# avr_plc.net
KiCad netlist of a schematic drawn in EAGLE
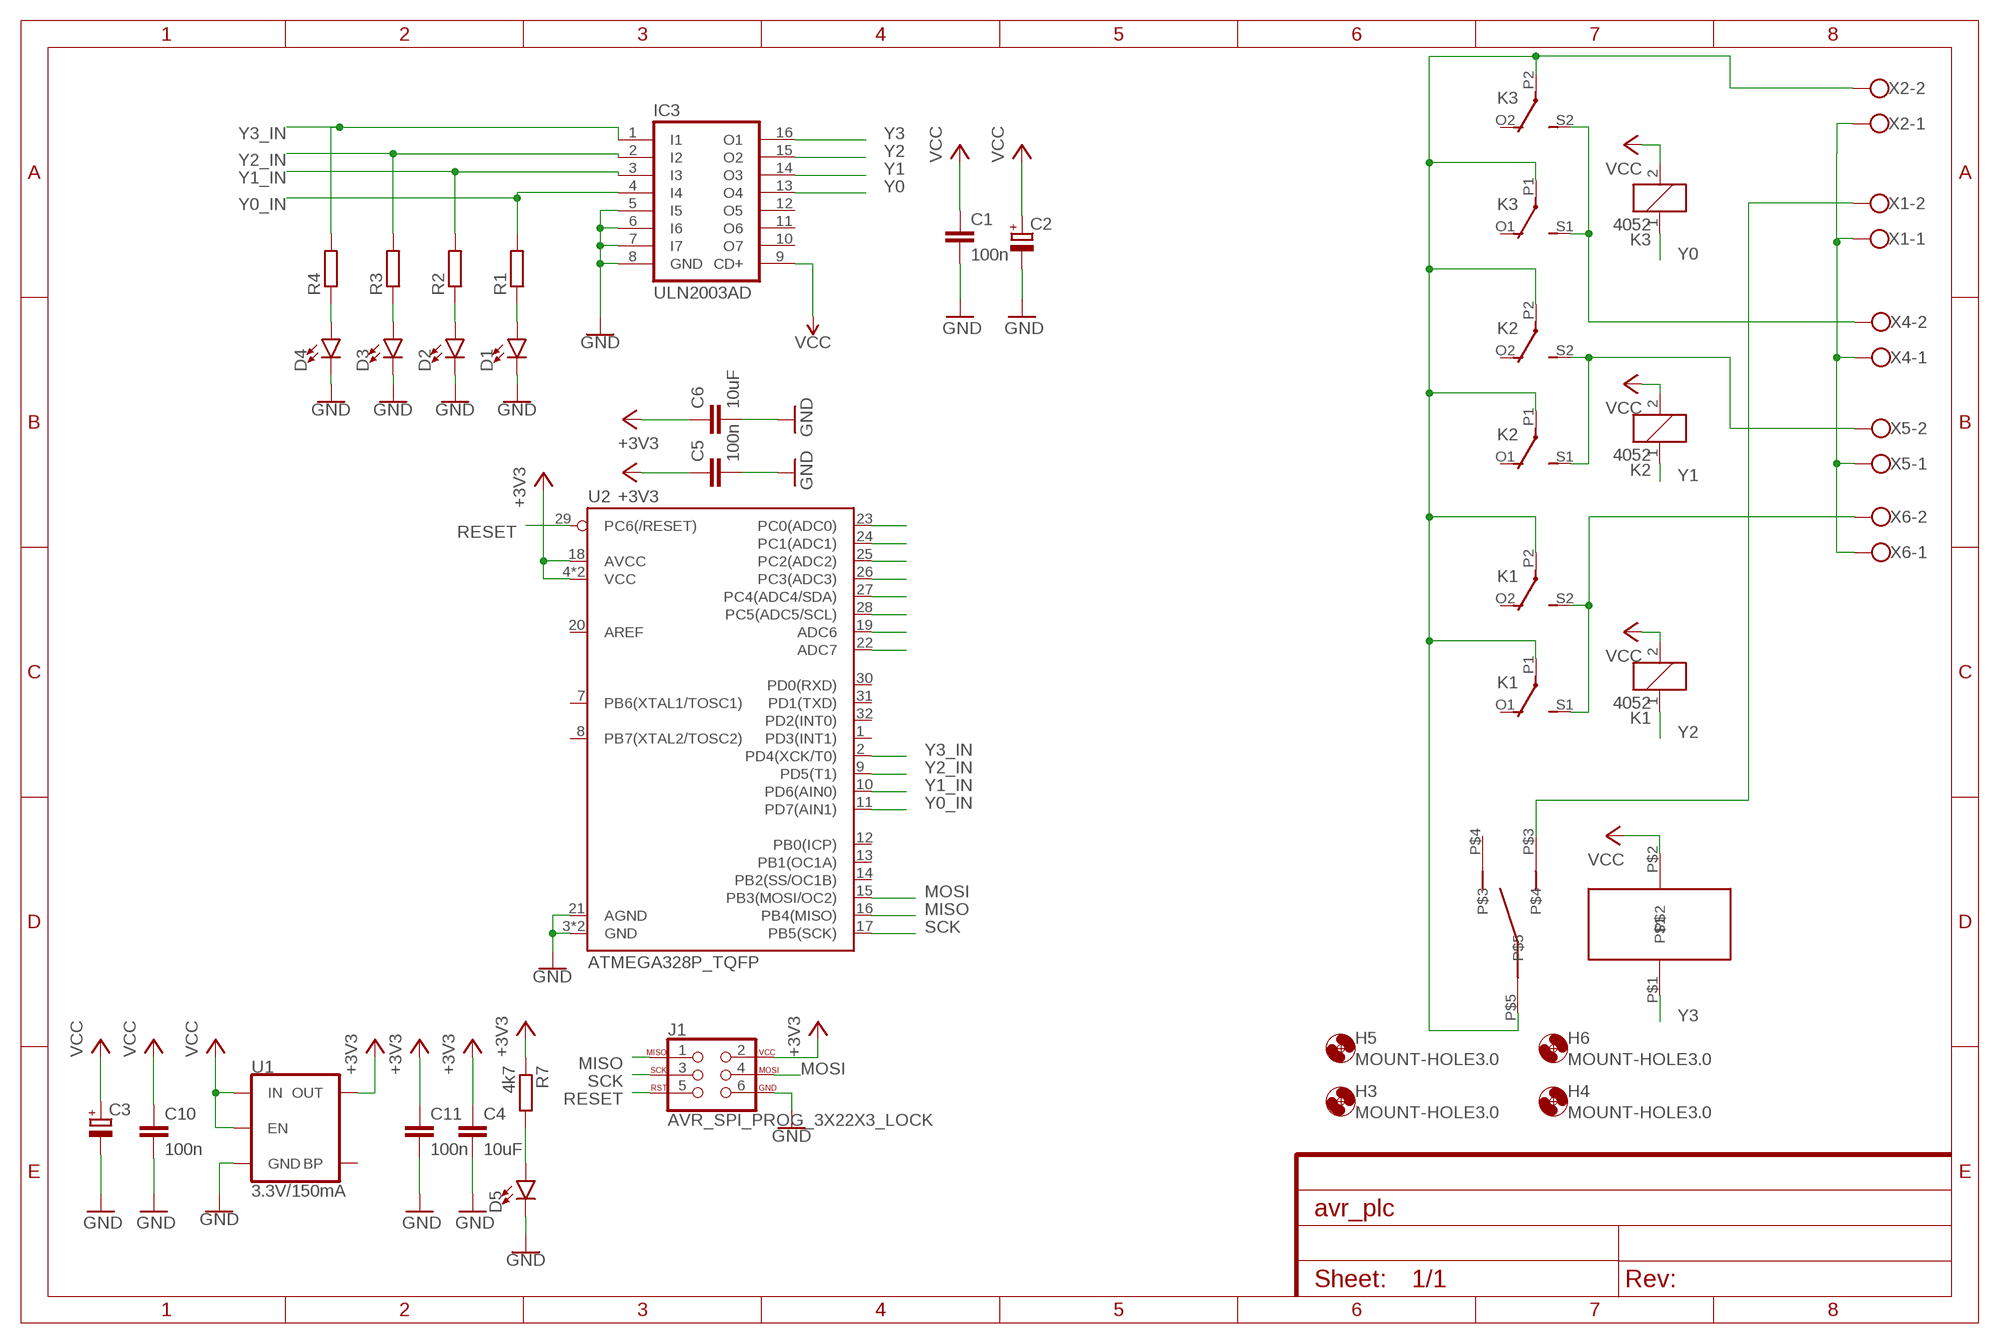
[diagram p0: schematic, sheet 1]

(export (version "E")
  (design (tool "Eeschema 10.0.6"))
  (components
    (comp (ref "C1")
      (value "100n")
      (footprint "eagle-import:C0805")
      (libsource (lib "eagle-import") (part "C-EUC0805"))
    )
    (comp (ref "C2")
      (value "CPOL-EU153CLV-0810")
      (footprint "eagle-import:153CLV-0810")
      (libsource (lib "eagle-import") (part "CPOL-EU153CLV-0810"))
    )
    (comp (ref "C3")
      (value "CPOL-EU153CLV-0810")
      (footprint "eagle-import:153CLV-0810")
      (libsource (lib "eagle-import") (part "CPOL-EU153CLV-0810"))
    )
    (comp (ref "C4")
      (value "10uF")
      (footprint "eagle-import:C0805")
      (libsource (lib "eagle-import") (part "C-EUC0805"))
    )
    (comp (ref "C5")
      (value "100n")
      (footprint "eagle-import:C0805")
      (libsource (lib "eagle-import") (part "C-EUC0805"))
    )
    (comp (ref "C6")
      (value "10uF")
      (footprint "eagle-import:C0805")
      (libsource (lib "eagle-import") (part "C-EUC0805"))
    )
    (comp (ref "C10")
      (value "100n")
      (footprint "eagle-import:C0805")
      (libsource (lib "eagle-import") (part "C-EUC0805"))
    )
    (comp (ref "C11")
      (value "100n")
      (footprint "eagle-import:C0805")
      (libsource (lib "eagle-import") (part "C-EUC0805"))
    )
    (comp (ref "D1")
      (value "LED1206")
      (footprint "eagle-import:LED-1206")
      (libsource (lib "eagle-import") (part "LED1206"))
    )
    (comp (ref "D2")
      (value "LED1206")
      (footprint "eagle-import:LED-1206")
      (libsource (lib "eagle-import") (part "LED1206"))
    )
    (comp (ref "D3")
      (value "LED1206")
      (footprint "eagle-import:LED-1206")
      (libsource (lib "eagle-import") (part "LED1206"))
    )
    (comp (ref "D4")
      (value "LED1206")
      (footprint "eagle-import:LED-1206")
      (libsource (lib "eagle-import") (part "LED1206"))
    )
    (comp (ref "D5")
      (value "LED1206")
      (footprint "eagle-import:LED-1206")
      (libsource (lib "eagle-import") (part "LED1206"))
    )
    (comp (ref "H3")
      (value "MOUNT-HOLE3.0")
      (footprint "eagle-import:3,0")
      (libsource (lib "eagle-import") (part "MOUNT-HOLE3.0"))
    )
    (comp (ref "H4")
      (value "MOUNT-HOLE3.0")
      (footprint "eagle-import:3,0")
      (libsource (lib "eagle-import") (part "MOUNT-HOLE3.0"))
    )
    (comp (ref "H5")
      (value "MOUNT-HOLE3.0")
      (footprint "eagle-import:3,0")
      (libsource (lib "eagle-import") (part "MOUNT-HOLE3.0"))
    )
    (comp (ref "H6")
      (value "MOUNT-HOLE3.0")
      (footprint "eagle-import:3,0")
      (libsource (lib "eagle-import") (part "MOUNT-HOLE3.0"))
    )
    (comp (ref "IC3")
      (value "ULN2003AD")
      (footprint "eagle-import:SO16")
      (libsource (lib "eagle-import") (part "ULN2003AD"))
    )
    (comp (ref "J1")
      (value "AVR_SPI_PROG_3X22X3_LOCK")
      (footprint "eagle-import:2X3_LOCK")
      (libsource (lib "eagle-import") (part "AVR_SPI_PROG_3X22X3_LOCK"))
    )
    (comp (ref "K1")
      (value "4052")
      (footprint "eagle-import:F4052")
      (libsource (lib "eagle-import") (part "4052"))
    )
    (comp (ref "K2")
      (value "4052")
      (footprint "eagle-import:F4052")
      (libsource (lib "eagle-import") (part "4052"))
    )
    (comp (ref "K3")
      (value "4052")
      (footprint "eagle-import:F4052")
      (libsource (lib "eagle-import") (part "4052"))
    )
    (comp (ref "R1")
      (value "R-EU_R0805")
      (footprint "eagle-import:R0805")
      (libsource (lib "eagle-import") (part "R-EU_R0805"))
    )
    (comp (ref "R2")
      (value "R-EU_R0805")
      (footprint "eagle-import:R0805")
      (libsource (lib "eagle-import") (part "R-EU_R0805"))
    )
    (comp (ref "R3")
      (value "R-EU_R0805")
      (footprint "eagle-import:R0805")
      (libsource (lib "eagle-import") (part "R-EU_R0805"))
    )
    (comp (ref "R4")
      (value "R-EU_R0805")
      (footprint "eagle-import:R0805")
      (libsource (lib "eagle-import") (part "R-EU_R0805"))
    )
    (comp (ref "R7")
      (value "4k7")
      (footprint "eagle-import:M0805")
      (libsource (lib "eagle-import") (part "R-EU_M0805"))
    )
    (comp (ref "U$1")
      (value "T9G_RELAY")
      (footprint "eagle-import:T9G_RELAY")
      (libsource (lib "eagle-import") (part "T9G_RELAY"))
    )
    (comp (ref "U1")
      (value "3.3V/150mA")
      (footprint "eagle-import:SOT23-5")
      (libsource (lib "eagle-import") (part "V_REG_MIC52053.3V"))
    )
    (comp (ref "U2")
      (value "ATMEGA328P_TQFP")
      (footprint "eagle-import:TQFP32-08")
      (libsource (lib "eagle-import") (part "ATMEGA328P_TQFP"))
    )
    (comp (ref "X1")
      (value "W239-302")
      (footprint "eagle-import:W239-302")
      (libsource (lib "eagle-import") (part "W239-302"))
    )
    (comp (ref "X2")
      (value "W239-302")
      (footprint "eagle-import:W239-302")
      (libsource (lib "eagle-import") (part "W239-302"))
    )
    (comp (ref "X4")
      (value "W237-102")
      (footprint "eagle-import:W237-102")
      (fields (field (name "MPN") "237-102"))
      (libsource (lib "eagle-import") (part "W237-102"))
    )
    (comp (ref "X5")
      (value "W237-102")
      (footprint "eagle-import:W237-102")
      (fields (field (name "MPN") "237-102"))
      (libsource (lib "eagle-import") (part "W237-102"))
    )
    (comp (ref "X6")
      (value "W237-102")
      (footprint "eagle-import:W237-102")
      (fields (field (name "MPN") "237-102"))
      (libsource (lib "eagle-import") (part "W237-102"))
    )
  )
  (nets
    (net (code "1") (name "+3V3") (class "Default")
      (node (ref "C11") (pin "1") (pinfunction "1_1") (pintype "passive"))
      (node (ref "C4") (pin "1") (pinfunction "1_1") (pintype "passive"))
      (node (ref "C5") (pin "1") (pinfunction "1_1") (pintype "passive"))
      (node (ref "C6") (pin "1") (pinfunction "1_1") (pintype "passive"))
      (node (ref "J1") (pin "2") (pinfunction "2_2") (pintype "passive"))
      (node (ref "R7") (pin "1") (pinfunction "1_1") (pintype "passive"))
      (node (ref "U1") (pin "5") (pinfunction "OUT_5") (pintype "passive"))
      (node (ref "U2") (pin "18") (pinfunction "AVCC_18") (pintype "bidirectional"))
      (node (ref "U2") (pin "4") (pinfunction "VCC_4") (pintype "bidirectional"))
      (node (ref "U2") (pin "6") (pinfunction "VCC_6") (pintype "bidirectional"))
    )
    (net (code "2") (name "/MISO") (class "Default")
      (node (ref "J1") (pin "1") (pinfunction "1_1") (pintype "passive"))
      (node (ref "U2") (pin "16") (pinfunction "PB4(MISO)_16") (pintype "bidirectional"))
    )
    (net (code "3") (name "/MOSI") (class "Default")
      (node (ref "J1") (pin "4") (pinfunction "4_4") (pintype "passive"))
      (node (ref "U2") (pin "15") (pinfunction "PB3(MOSI/OC2)_15") (pintype "bidirectional"))
    )
    (net (code "4") (name "/RESET") (class "Default")
      (node (ref "J1") (pin "5") (pinfunction "5_5") (pintype "passive"))
      (node (ref "U2") (pin "29") (pinfunction "PC6(/RESET)_29") (pintype "bidirectional"))
    )
    (net (code "5") (name "/SCK") (class "Default")
      (node (ref "J1") (pin "3") (pinfunction "3_3") (pintype "passive"))
      (node (ref "U2") (pin "17") (pinfunction "PB5(SCK)_17") (pintype "bidirectional"))
    )
    (net (code "6") (name "/Y0") (class "Default")
      (node (ref "IC3") (pin "13") (pinfunction "O4_13") (pintype "open_collector"))
      (node (ref "K3") (pin "1") (pinfunction "1_1") (pintype "passive"))
    )
    (net (code "7") (name "/Y0_IN") (class "Default")
      (node (ref "IC3") (pin "4") (pinfunction "I4_4") (pintype "input"))
      (node (ref "R1") (pin "2") (pinfunction "2_2") (pintype "passive"))
      (node (ref "U2") (pin "11") (pinfunction "PD7(AIN1)_11") (pintype "bidirectional"))
    )
    (net (code "8") (name "/Y1") (class "Default")
      (node (ref "IC3") (pin "14") (pinfunction "O3_14") (pintype "open_collector"))
      (node (ref "K2") (pin "1") (pinfunction "1_1") (pintype "passive"))
    )
    (net (code "9") (name "/Y1_IN") (class "Default")
      (node (ref "IC3") (pin "3") (pinfunction "I3_3") (pintype "input"))
      (node (ref "R2") (pin "2") (pinfunction "2_2") (pintype "passive"))
      (node (ref "U2") (pin "10") (pinfunction "PD6(AIN0)_10") (pintype "bidirectional"))
    )
    (net (code "10") (name "/Y2") (class "Default")
      (node (ref "IC3") (pin "15") (pinfunction "O2_15") (pintype "open_collector"))
      (node (ref "K1") (pin "1") (pinfunction "1_1") (pintype "passive"))
    )
    (net (code "11") (name "/Y2_IN") (class "Default")
      (node (ref "IC3") (pin "2") (pinfunction "I2_2") (pintype "input"))
      (node (ref "R3") (pin "2") (pinfunction "2_2") (pintype "passive"))
      (node (ref "U2") (pin "9") (pinfunction "PD5(T1)_9") (pintype "bidirectional"))
    )
    (net (code "12") (name "/Y3") (class "Default")
      (node (ref "IC3") (pin "16") (pinfunction "O1_16") (pintype "open_collector"))
      (node (ref "U$1") (pin "P$1") (pinfunction "P$1_P$1") (pintype "bidirectional"))
    )
    (net (code "13") (name "/Y3_IN") (class "Default")
      (node (ref "IC3") (pin "1") (pinfunction "I1_1") (pintype "input"))
      (node (ref "R4") (pin "2") (pinfunction "2_2") (pintype "passive"))
      (node (ref "U2") (pin "2") (pinfunction "PD4(XCK/T0)_2") (pintype "bidirectional"))
    )
    (net (code "14") (name "GND") (class "Default")
      (node (ref "C1") (pin "2") (pinfunction "2_2") (pintype "passive"))
      (node (ref "C10") (pin "2") (pinfunction "2_2") (pintype "passive"))
      (node (ref "C11") (pin "2") (pinfunction "2_2") (pintype "passive"))
      (node (ref "C2") (pin "-") (pinfunction "-_-") (pintype "passive"))
      (node (ref "C3") (pin "-") (pinfunction "-_-") (pintype "passive"))
      (node (ref "C4") (pin "2") (pinfunction "2_2") (pintype "passive"))
      (node (ref "C5") (pin "2") (pinfunction "2_2") (pintype "passive"))
      (node (ref "C6") (pin "2") (pinfunction "2_2") (pintype "passive"))
      (node (ref "D1") (pin "C") (pinfunction "C_C") (pintype "passive"))
      (node (ref "D2") (pin "C") (pinfunction "C_C") (pintype "passive"))
      (node (ref "D3") (pin "C") (pinfunction "C_C") (pintype "passive"))
      (node (ref "D4") (pin "C") (pinfunction "C_C") (pintype "passive"))
      (node (ref "D5") (pin "C") (pinfunction "C_C") (pintype "passive"))
      (node (ref "IC3") (pin "5") (pinfunction "I5_5") (pintype "input"))
      (node (ref "IC3") (pin "6") (pinfunction "I6_6") (pintype "input"))
      (node (ref "IC3") (pin "7") (pinfunction "I7_7") (pintype "input"))
      (node (ref "IC3") (pin "8") (pinfunction "GND_8") (pintype "power_in"))
      (node (ref "J1") (pin "6") (pinfunction "6_6") (pintype "passive"))
      (node (ref "U1") (pin "2") (pinfunction "GND_2") (pintype "input"))
      (node (ref "U2") (pin "21") (pinfunction "AGND_21") (pintype "bidirectional"))
      (node (ref "U2") (pin "3") (pinfunction "GND_3") (pintype "bidirectional"))
      (node (ref "U2") (pin "5") (pinfunction "GND_5") (pintype "bidirectional"))
    )
    (net (code "15") (name "Net-(D1-PadA)") (class "Default")
      (node (ref "D1") (pin "A") (pinfunction "A_A") (pintype "passive"))
      (node (ref "R1") (pin "1") (pinfunction "1_1") (pintype "passive"))
    )
    (net (code "16") (name "Net-(D2-PadA)") (class "Default")
      (node (ref "D2") (pin "A") (pinfunction "A_A") (pintype "passive"))
      (node (ref "R2") (pin "1") (pinfunction "1_1") (pintype "passive"))
    )
    (net (code "17") (name "Net-(D3-PadA)") (class "Default")
      (node (ref "D3") (pin "A") (pinfunction "A_A") (pintype "passive"))
      (node (ref "R3") (pin "1") (pinfunction "1_1") (pintype "passive"))
    )
    (net (code "18") (name "Net-(D4-PadA)") (class "Default")
      (node (ref "D4") (pin "A") (pinfunction "A_A") (pintype "passive"))
      (node (ref "R4") (pin "1") (pinfunction "1_1") (pintype "passive"))
    )
    (net (code "19") (name "Net-(D5-PadA)") (class "Default")
      (node (ref "D5") (pin "A") (pinfunction "A_A") (pintype "passive"))
      (node (ref "R7") (pin "2") (pinfunction "2_2") (pintype "passive"))
    )
    (net (code "20") (name "Net-(K1B-P)") (class "Default")
      (node (ref "K1") (pin "P1") (pinfunction "P_P1") (pintype "passive"))
      (node (ref "K1") (pin "P2") (pinfunction "P_P2") (pintype "passive"))
      (node (ref "K2") (pin "P1") (pinfunction "P_P1") (pintype "passive"))
      (node (ref "K2") (pin "P2") (pinfunction "P_P2") (pintype "passive"))
      (node (ref "K3") (pin "P1") (pinfunction "P_P1") (pintype "passive"))
      (node (ref "K3") (pin "P2") (pinfunction "P_P2") (pintype "passive"))
      (node (ref "U$1") (pin "P$5") (pinfunction "P$5_P$5") (pintype "bidirectional"))
      (node (ref "X2") (pin "2") (pinfunction "KL_2") (pintype "passive"))
    )
    (net (code "21") (name "Net-(K1B-S)") (class "Default")
      (node (ref "K1") (pin "S1") (pinfunction "S_S1") (pintype "passive"))
      (node (ref "K1") (pin "S2") (pinfunction "S_S2") (pintype "passive"))
      (node (ref "X6") (pin "2") (pinfunction "KL_2") (pintype "passive"))
    )
    (net (code "22") (name "Net-(K2B-S)") (class "Default")
      (node (ref "K2") (pin "S1") (pinfunction "S_S1") (pintype "passive"))
      (node (ref "K2") (pin "S2") (pinfunction "S_S2") (pintype "passive"))
      (node (ref "X5") (pin "2") (pinfunction "KL_2") (pintype "passive"))
    )
    (net (code "23") (name "Net-(K3B-S)") (class "Default")
      (node (ref "K3") (pin "S1") (pinfunction "S_S1") (pintype "passive"))
      (node (ref "K3") (pin "S2") (pinfunction "S_S2") (pintype "passive"))
      (node (ref "X4") (pin "2") (pinfunction "KL_2") (pintype "passive"))
    )
    (net (code "24") (name "Net-(U$1-P$4)") (class "Default")
      (node (ref "U$1") (pin "P$3") (pinfunction "P$4_P$3") (pintype "bidirectional"))
      (node (ref "X1") (pin "2") (pinfunction "KL_2") (pintype "passive"))
    )
    (net (code "25") (name "Net-(X1A-KL)") (class "Default")
      (node (ref "X1") (pin "1") (pinfunction "KL_1") (pintype "passive"))
      (node (ref "X2") (pin "1") (pinfunction "KL_1") (pintype "passive"))
      (node (ref "X4") (pin "1") (pinfunction "KL_1") (pintype "passive"))
      (node (ref "X5") (pin "1") (pinfunction "KL_1") (pintype "passive"))
      (node (ref "X6") (pin "1") (pinfunction "KL_1") (pintype "passive"))
    )
    (net (code "26") (name "VCC") (class "Default")
      (node (ref "C1") (pin "1") (pinfunction "1_1") (pintype "passive"))
      (node (ref "C10") (pin "1") (pinfunction "1_1") (pintype "passive"))
      (node (ref "C2") (pin "+") (pinfunction "+_+") (pintype "passive"))
      (node (ref "C3") (pin "+") (pinfunction "+_+") (pintype "passive"))
      (node (ref "IC3") (pin "9") (pinfunction "CD+_9") (pintype "passive"))
      (node (ref "K1") (pin "2") (pinfunction "2_2") (pintype "passive"))
      (node (ref "K2") (pin "2") (pinfunction "2_2") (pintype "passive"))
      (node (ref "K3") (pin "2") (pinfunction "2_2") (pintype "passive"))
      (node (ref "U$1") (pin "P$2") (pinfunction "P$2_P$2") (pintype "bidirectional"))
      (node (ref "U1") (pin "1") (pinfunction "IN_1") (pintype "input"))
      (node (ref "U1") (pin "3") (pinfunction "EN_3") (pintype "input"))
    )
    (net (code "27") (name "unconnected-(IC3-O5-Pad12)") (class "Default")
      (node (ref "IC3") (pin "12") (pinfunction "O5_12") (pintype "open_collector"))
    )
    (net (code "28") (name "unconnected-(IC3-O6-Pad11)") (class "Default")
      (node (ref "IC3") (pin "11") (pinfunction "O6_11") (pintype "open_collector"))
    )
    (net (code "29") (name "unconnected-(IC3-O7-Pad10)") (class "Default")
      (node (ref "IC3") (pin "10") (pinfunction "O7_10") (pintype "open_collector"))
    )
    (net (code "30") (name "unconnected-(K1B-O-PadO1)") (class "Default")
      (node (ref "K1") (pin "O1") (pinfunction "O_O1") (pintype "passive"))
    )
    (net (code "31") (name "unconnected-(K1C-O-PadO2)") (class "Default")
      (node (ref "K1") (pin "O2") (pinfunction "O_O2") (pintype "passive"))
    )
    (net (code "32") (name "unconnected-(K2B-O-PadO1)") (class "Default")
      (node (ref "K2") (pin "O1") (pinfunction "O_O1") (pintype "passive"))
    )
    (net (code "33") (name "unconnected-(K2C-O-PadO2)") (class "Default")
      (node (ref "K2") (pin "O2") (pinfunction "O_O2") (pintype "passive"))
    )
    (net (code "34") (name "unconnected-(K3B-O-PadO1)") (class "Default")
      (node (ref "K3") (pin "O1") (pinfunction "O_O1") (pintype "passive"))
    )
    (net (code "35") (name "unconnected-(K3C-O-PadO2)") (class "Default")
      (node (ref "K3") (pin "O2") (pinfunction "O_O2") (pintype "passive"))
    )
    (net (code "36") (name "unconnected-(U$1-P$3-PadP$4)") (class "Default")
      (node (ref "U$1") (pin "P$4") (pinfunction "P$3_P$4") (pintype "bidirectional"))
    )
    (net (code "37") (name "unconnected-(U1-BP-Pad4)") (class "Default")
      (node (ref "U1") (pin "4") (pinfunction "BP_4") (pintype "input"))
    )
    (net (code "38") (name "unconnected-(U2-ADC6-Pad19)") (class "Default")
      (node (ref "U2") (pin "19") (pinfunction "ADC6_19") (pintype "bidirectional"))
    )
    (net (code "39") (name "unconnected-(U2-ADC7-Pad22)") (class "Default")
      (node (ref "U2") (pin "22") (pinfunction "ADC7_22") (pintype "bidirectional"))
    )
    (net (code "40") (name "unconnected-(U2-AREF-Pad20)") (class "Default")
      (node (ref "U2") (pin "20") (pinfunction "AREF_20") (pintype "bidirectional"))
    )
    (net (code "41") (name "unconnected-(U2-PB0(ICP)-Pad12)") (class "Default")
      (node (ref "U2") (pin "12") (pinfunction "PB0(ICP)_12") (pintype "bidirectional"))
    )
    (net (code "42") (name "unconnected-(U2-PB1(OC1A)-Pad13)") (class "Default")
      (node (ref "U2") (pin "13") (pinfunction "PB1(OC1A)_13") (pintype "bidirectional"))
    )
    (net (code "43") (name "unconnected-(U2-PB2(SS{slash}OC1B)-Pad14)") (class "Default")
      (node (ref "U2") (pin "14") (pinfunction "PB2(SS/OC1B)_14") (pintype "bidirectional"))
    )
    (net (code "44") (name "unconnected-(U2-PB6(XTAL1{slash}TOSC1)-Pad7)") (class "Default")
      (node (ref "U2") (pin "7") (pinfunction "PB6(XTAL1/TOSC1)_7") (pintype "bidirectional"))
    )
    (net (code "45") (name "unconnected-(U2-PB7(XTAL2{slash}TOSC2)-Pad8)") (class "Default")
      (node (ref "U2") (pin "8") (pinfunction "PB7(XTAL2/TOSC2)_8") (pintype "bidirectional"))
    )
    (net (code "46") (name "unconnected-(U2-PC0(ADC0)-Pad23)") (class "Default")
      (node (ref "U2") (pin "23") (pinfunction "PC0(ADC0)_23") (pintype "bidirectional"))
    )
    (net (code "47") (name "unconnected-(U2-PC1(ADC1)-Pad24)") (class "Default")
      (node (ref "U2") (pin "24") (pinfunction "PC1(ADC1)_24") (pintype "bidirectional"))
    )
    (net (code "48") (name "unconnected-(U2-PC2(ADC2)-Pad25)") (class "Default")
      (node (ref "U2") (pin "25") (pinfunction "PC2(ADC2)_25") (pintype "bidirectional"))
    )
    (net (code "49") (name "unconnected-(U2-PC3(ADC3)-Pad26)") (class "Default")
      (node (ref "U2") (pin "26") (pinfunction "PC3(ADC3)_26") (pintype "bidirectional"))
    )
    (net (code "50") (name "unconnected-(U2-PC4(ADC4{slash}SDA)-Pad27)") (class "Default")
      (node (ref "U2") (pin "27") (pinfunction "PC4(ADC4/SDA)_27") (pintype "bidirectional"))
    )
    (net (code "51") (name "unconnected-(U2-PC5(ADC5{slash}SCL)-Pad28)") (class "Default")
      (node (ref "U2") (pin "28") (pinfunction "PC5(ADC5/SCL)_28") (pintype "bidirectional"))
    )
    (net (code "52") (name "unconnected-(U2-PD0(RXD)-Pad30)") (class "Default")
      (node (ref "U2") (pin "30") (pinfunction "PD0(RXD)_30") (pintype "bidirectional"))
    )
    (net (code "53") (name "unconnected-(U2-PD1(TXD)-Pad31)") (class "Default")
      (node (ref "U2") (pin "31") (pinfunction "PD1(TXD)_31") (pintype "bidirectional"))
    )
    (net (code "54") (name "unconnected-(U2-PD2(INT0)-Pad32)") (class "Default")
      (node (ref "U2") (pin "32") (pinfunction "PD2(INT0)_32") (pintype "bidirectional"))
    )
    (net (code "55") (name "unconnected-(U2-PD3(INT1)-Pad1)") (class "Default")
      (node (ref "U2") (pin "1") (pinfunction "PD3(INT1)_1") (pintype "bidirectional"))
    )
  )
)
